# LED_Controller.net
KiCad netlist of a schematic drawn in EAGLE
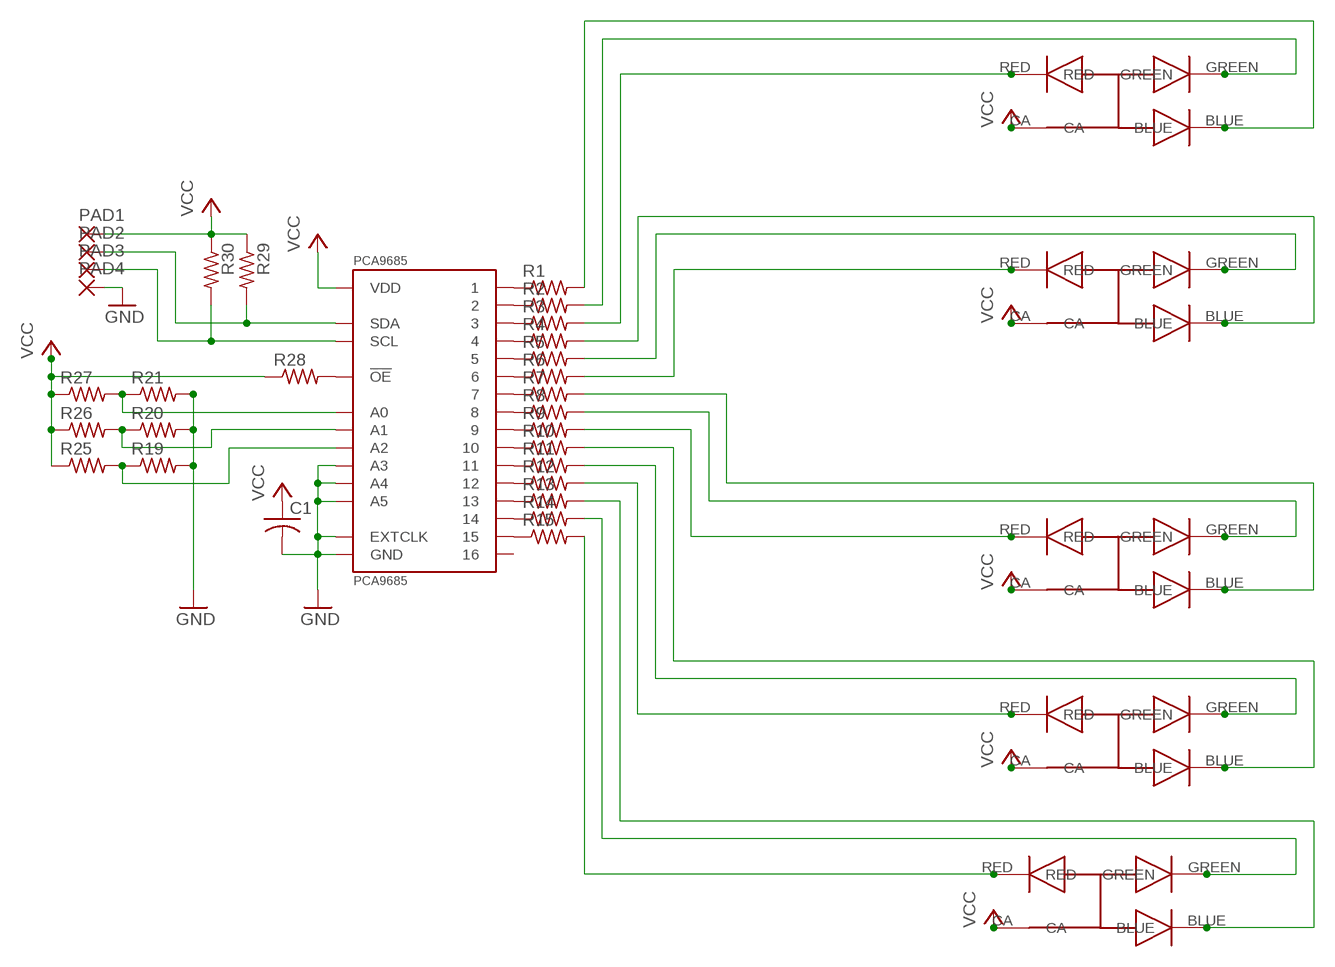
[diagram p0: schematic, sheet 1]

(export (version "E")
  (design (tool "Eeschema 10.0.6"))
  (components
    (comp (ref "C1")
      (value "C-USC0402")
      (footprint "eagle-import:C0402")
      (libsource (lib "eagle-import") (part "C-USC0402"))
    )
    (comp (ref "PAD1")
      (value "SMD2")
      (footprint "eagle-import:SMD1,27-2,54")
      (libsource (lib "eagle-import") (part "SMD2"))
    )
    (comp (ref "PAD2")
      (value "SMD2")
      (footprint "eagle-import:SMD1,27-2,54")
      (libsource (lib "eagle-import") (part "SMD2"))
    )
    (comp (ref "PAD3")
      (value "SMD2")
      (footprint "eagle-import:SMD1,27-2,54")
      (libsource (lib "eagle-import") (part "SMD2"))
    )
    (comp (ref "PAD4")
      (value "SMD2")
      (footprint "eagle-import:SMD1,27-2,54")
      (libsource (lib "eagle-import") (part "SMD2"))
    )
    (comp (ref "PCA9685")
      (value "PCA9685")
      (footprint "eagle-import:HVQFN28")
      (libsource (lib "eagle-import") (part "PCA9685"))
    )
    (comp (ref "R1")
      (value "R-US_R0402")
      (footprint "eagle-import:R0402")
      (libsource (lib "eagle-import") (part "R-US_R0402"))
    )
    (comp (ref "R2")
      (value "R-US_R0402")
      (footprint "eagle-import:R0402")
      (libsource (lib "eagle-import") (part "R-US_R0402"))
    )
    (comp (ref "R3")
      (value "R-US_R0402")
      (footprint "eagle-import:R0402")
      (libsource (lib "eagle-import") (part "R-US_R0402"))
    )
    (comp (ref "R4")
      (value "R-US_R0402")
      (footprint "eagle-import:R0402")
      (libsource (lib "eagle-import") (part "R-US_R0402"))
    )
    (comp (ref "R5")
      (value "R-US_R0402")
      (footprint "eagle-import:R0402")
      (libsource (lib "eagle-import") (part "R-US_R0402"))
    )
    (comp (ref "R6")
      (value "R-US_R0402")
      (footprint "eagle-import:R0402")
      (libsource (lib "eagle-import") (part "R-US_R0402"))
    )
    (comp (ref "R7")
      (value "R-US_R0402")
      (footprint "eagle-import:R0402")
      (libsource (lib "eagle-import") (part "R-US_R0402"))
    )
    (comp (ref "R8")
      (value "R-US_R0402")
      (footprint "eagle-import:R0402")
      (libsource (lib "eagle-import") (part "R-US_R0402"))
    )
    (comp (ref "R9")
      (value "R-US_R0402")
      (footprint "eagle-import:R0402")
      (libsource (lib "eagle-import") (part "R-US_R0402"))
    )
    (comp (ref "R10")
      (value "R-US_R0402")
      (footprint "eagle-import:R0402")
      (libsource (lib "eagle-import") (part "R-US_R0402"))
    )
    (comp (ref "R11")
      (value "R-US_R0402")
      (footprint "eagle-import:R0402")
      (libsource (lib "eagle-import") (part "R-US_R0402"))
    )
    (comp (ref "R12")
      (value "R-US_R0402")
      (footprint "eagle-import:R0402")
      (libsource (lib "eagle-import") (part "R-US_R0402"))
    )
    (comp (ref "R13")
      (value "R-US_R0402")
      (footprint "eagle-import:R0402")
      (libsource (lib "eagle-import") (part "R-US_R0402"))
    )
    (comp (ref "R14")
      (value "R-US_R0402")
      (footprint "eagle-import:R0402")
      (libsource (lib "eagle-import") (part "R-US_R0402"))
    )
    (comp (ref "R15")
      (value "R-US_R0402")
      (footprint "eagle-import:R0402")
      (libsource (lib "eagle-import") (part "R-US_R0402"))
    )
    (comp (ref "R19")
      (value "R-US_R0402")
      (footprint "eagle-import:R0402")
      (libsource (lib "eagle-import") (part "R-US_R0402"))
    )
    (comp (ref "R20")
      (value "R-US_R0402")
      (footprint "eagle-import:R0402")
      (libsource (lib "eagle-import") (part "R-US_R0402"))
    )
    (comp (ref "R21")
      (value "R-US_R0402")
      (footprint "eagle-import:R0402")
      (libsource (lib "eagle-import") (part "R-US_R0402"))
    )
    (comp (ref "R25")
      (value "R-US_R0402")
      (footprint "eagle-import:R0402")
      (libsource (lib "eagle-import") (part "R-US_R0402"))
    )
    (comp (ref "R26")
      (value "R-US_R0402")
      (footprint "eagle-import:R0402")
      (libsource (lib "eagle-import") (part "R-US_R0402"))
    )
    (comp (ref "R27")
      (value "R-US_R0402")
      (footprint "eagle-import:R0402")
      (libsource (lib "eagle-import") (part "R-US_R0402"))
    )
    (comp (ref "R28")
      (value "R-US_R0402")
      (footprint "eagle-import:R0402")
      (libsource (lib "eagle-import") (part "R-US_R0402"))
    )
    (comp (ref "R29")
      (value "R-US_R0402")
      (footprint "eagle-import:R0402")
      (libsource (lib "eagle-import") (part "R-US_R0402"))
    )
    (comp (ref "R30")
      (value "R-US_R0402")
      (footprint "eagle-import:R0402")
      (libsource (lib "eagle-import") (part "R-US_R0402"))
    )
    (comp (ref "U$2")
      (value "CLV1A-FKB")
      (footprint "eagle-import:CLV1A-FKB")
      (libsource (lib "eagle-import") (part "CLV1A-FKB"))
    )
    (comp (ref "U$3")
      (value "CLV1A-FKB")
      (footprint "eagle-import:CLV1A-FKB")
      (libsource (lib "eagle-import") (part "CLV1A-FKB"))
    )
    (comp (ref "U$4")
      (value "CLV1A-FKB")
      (footprint "eagle-import:CLV1A-FKB")
      (libsource (lib "eagle-import") (part "CLV1A-FKB"))
    )
    (comp (ref "U$5")
      (value "CLV1A-FKB")
      (footprint "eagle-import:CLV1A-FKB")
      (libsource (lib "eagle-import") (part "CLV1A-FKB"))
    )
    (comp (ref "U$6")
      (value "CLV1A-FKB")
      (footprint "eagle-import:CLV1A-FKB")
      (libsource (lib "eagle-import") (part "CLV1A-FKB"))
    )
  )
  (nets
    (net (code "1") (name "GND") (class "Default")
      (node (ref "C1") (pin "2") (pinfunction "2_2") (pintype "passive"))
      (node (ref "PAD4") (pin "1") (pinfunction "P_1") (pintype "passive"))
      (node (ref "PCA9685") (pin "14") (pinfunction "GND_14") (pintype "bidirectional"))
      (node (ref "PCA9685") (pin "24") (pinfunction "A5_24") (pintype "bidirectional"))
      (node (ref "PCA9685") (pin "25") (pinfunction "EXTCLK_25") (pintype "bidirectional"))
      (node (ref "PCA9685") (pin "4") (pinfunction "A3_4") (pintype "bidirectional"))
      (node (ref "PCA9685") (pin "5") (pinfunction "A4_5") (pintype "bidirectional"))
      (node (ref "PCA9685") (pin "PAD") (pinfunction "GND_PAD") (pintype "bidirectional"))
      (node (ref "R19") (pin "2") (pinfunction "2_2") (pintype "passive"))
      (node (ref "R20") (pin "2") (pinfunction "2_2") (pintype "passive"))
      (node (ref "R21") (pin "2") (pinfunction "2_2") (pintype "passive"))
    )
    (net (code "2") (name "Net-(PAD2-P)") (class "Default")
      (node (ref "PAD2") (pin "1") (pinfunction "P_1") (pintype "passive"))
      (node (ref "PCA9685") (pin "27") (pinfunction "SDA_27") (pintype "bidirectional"))
      (node (ref "R29") (pin "2") (pinfunction "2_2") (pintype "passive"))
    )
    (net (code "3") (name "Net-(PAD3-P)") (class "Default")
      (node (ref "PAD3") (pin "1") (pinfunction "P_1") (pintype "passive"))
      (node (ref "PCA9685") (pin "26") (pinfunction "SCL_26") (pintype "bidirectional"))
      (node (ref "R30") (pin "2") (pinfunction "2_2") (pintype "passive"))
    )
    (net (code "4") (name "Net-(PCA9685-1)") (class "Default")
      (node (ref "PCA9685") (pin "6") (pinfunction "1_6") (pintype "bidirectional"))
      (node (ref "R1") (pin "1") (pinfunction "1_1") (pintype "passive"))
    )
    (net (code "5") (name "Net-(PCA9685-2)") (class "Default")
      (node (ref "PCA9685") (pin "7") (pinfunction "2_7") (pintype "bidirectional"))
      (node (ref "R2") (pin "1") (pinfunction "1_1") (pintype "passive"))
    )
    (net (code "6") (name "Net-(PCA9685-3)") (class "Default")
      (node (ref "PCA9685") (pin "8") (pinfunction "3_8") (pintype "bidirectional"))
      (node (ref "R3") (pin "1") (pinfunction "1_1") (pintype "passive"))
    )
    (net (code "7") (name "Net-(PCA9685-4)") (class "Default")
      (node (ref "PCA9685") (pin "9") (pinfunction "4_9") (pintype "bidirectional"))
      (node (ref "R4") (pin "1") (pinfunction "1_1") (pintype "passive"))
    )
    (net (code "8") (name "Net-(PCA9685-5)") (class "Default")
      (node (ref "PCA9685") (pin "10") (pinfunction "5_10") (pintype "bidirectional"))
      (node (ref "R5") (pin "1") (pinfunction "1_1") (pintype "passive"))
    )
    (net (code "9") (name "Net-(PCA9685-6)") (class "Default")
      (node (ref "PCA9685") (pin "11") (pinfunction "6_11") (pintype "bidirectional"))
      (node (ref "R6") (pin "1") (pinfunction "1_1") (pintype "passive"))
    )
    (net (code "10") (name "Net-(PCA9685-7)") (class "Default")
      (node (ref "PCA9685") (pin "12") (pinfunction "7_12") (pintype "bidirectional"))
      (node (ref "R7") (pin "1") (pinfunction "1_1") (pintype "passive"))
    )
    (net (code "11") (name "Net-(PCA9685-8)") (class "Default")
      (node (ref "PCA9685") (pin "13") (pinfunction "8_13") (pintype "bidirectional"))
      (node (ref "R8") (pin "1") (pinfunction "1_1") (pintype "passive"))
    )
    (net (code "12") (name "Net-(PCA9685-9)") (class "Default")
      (node (ref "PCA9685") (pin "15") (pinfunction "9_15") (pintype "bidirectional"))
      (node (ref "R9") (pin "1") (pinfunction "1_1") (pintype "passive"))
    )
    (net (code "13") (name "Net-(PCA9685-10)") (class "Default")
      (node (ref "PCA9685") (pin "16") (pinfunction "10_16") (pintype "bidirectional"))
      (node (ref "R10") (pin "1") (pinfunction "1_1") (pintype "passive"))
    )
    (net (code "14") (name "Net-(PCA9685-11)") (class "Default")
      (node (ref "PCA9685") (pin "17") (pinfunction "11_17") (pintype "bidirectional"))
      (node (ref "R11") (pin "1") (pinfunction "1_1") (pintype "passive"))
    )
    (net (code "15") (name "Net-(PCA9685-12)") (class "Default")
      (node (ref "PCA9685") (pin "18") (pinfunction "12_18") (pintype "bidirectional"))
      (node (ref "R12") (pin "1") (pinfunction "1_1") (pintype "passive"))
    )
    (net (code "16") (name "Net-(PCA9685-13)") (class "Default")
      (node (ref "PCA9685") (pin "19") (pinfunction "13_19") (pintype "bidirectional"))
      (node (ref "R13") (pin "1") (pinfunction "1_1") (pintype "passive"))
    )
    (net (code "17") (name "Net-(PCA9685-14)") (class "Default")
      (node (ref "PCA9685") (pin "20") (pinfunction "14_20") (pintype "bidirectional"))
      (node (ref "R14") (pin "1") (pinfunction "1_1") (pintype "passive"))
    )
    (net (code "18") (name "Net-(PCA9685-15)") (class "Default")
      (node (ref "PCA9685") (pin "21") (pinfunction "15_21") (pintype "bidirectional"))
      (node (ref "R15") (pin "1") (pinfunction "1_1") (pintype "passive"))
    )
    (net (code "19") (name "Net-(PCA9685-A0)") (class "Default")
      (node (ref "PCA9685") (pin "1") (pinfunction "A0_1") (pintype "bidirectional"))
      (node (ref "R21") (pin "1") (pinfunction "1_1") (pintype "passive"))
      (node (ref "R27") (pin "2") (pinfunction "2_2") (pintype "passive"))
    )
    (net (code "20") (name "Net-(PCA9685-A1)") (class "Default")
      (node (ref "PCA9685") (pin "2") (pinfunction "A1_2") (pintype "bidirectional"))
      (node (ref "R20") (pin "1") (pinfunction "1_1") (pintype "passive"))
      (node (ref "R26") (pin "2") (pinfunction "2_2") (pintype "passive"))
    )
    (net (code "21") (name "Net-(PCA9685-A2)") (class "Default")
      (node (ref "PCA9685") (pin "3") (pinfunction "A2_3") (pintype "bidirectional"))
      (node (ref "R19") (pin "1") (pinfunction "1_1") (pintype "passive"))
      (node (ref "R25") (pin "2") (pinfunction "2_2") (pintype "passive"))
    )
    (net (code "22") (name "Net-(PCA9685-~{OE})") (class "Default")
      (node (ref "PCA9685") (pin "23") (pinfunction "~{OE}_23") (pintype "bidirectional"))
      (node (ref "R28") (pin "2") (pinfunction "2_2") (pintype "passive"))
    )
    (net (code "23") (name "Net-(R1-Pad2)") (class "Default")
      (node (ref "R1") (pin "2") (pinfunction "2_2") (pintype "passive"))
      (node (ref "U$6") (pin "BLUE") (pinfunction "BLUE_BLUE") (pintype "bidirectional"))
    )
    (net (code "24") (name "Net-(R2-Pad2)") (class "Default")
      (node (ref "R2") (pin "2") (pinfunction "2_2") (pintype "passive"))
      (node (ref "U$6") (pin "GREEN") (pinfunction "GREEN_GREEN") (pintype "bidirectional"))
    )
    (net (code "25") (name "Net-(R3-Pad2)") (class "Default")
      (node (ref "R3") (pin "2") (pinfunction "2_2") (pintype "passive"))
      (node (ref "U$6") (pin "RED") (pinfunction "RED_RED") (pintype "bidirectional"))
    )
    (net (code "26") (name "Net-(R4-Pad2)") (class "Default")
      (node (ref "R4") (pin "2") (pinfunction "2_2") (pintype "passive"))
      (node (ref "U$5") (pin "BLUE") (pinfunction "BLUE_BLUE") (pintype "bidirectional"))
    )
    (net (code "27") (name "Net-(R5-Pad2)") (class "Default")
      (node (ref "R5") (pin "2") (pinfunction "2_2") (pintype "passive"))
      (node (ref "U$5") (pin "GREEN") (pinfunction "GREEN_GREEN") (pintype "bidirectional"))
    )
    (net (code "28") (name "Net-(R6-Pad2)") (class "Default")
      (node (ref "R6") (pin "2") (pinfunction "2_2") (pintype "passive"))
      (node (ref "U$5") (pin "RED") (pinfunction "RED_RED") (pintype "bidirectional"))
    )
    (net (code "29") (name "Net-(R7-Pad2)") (class "Default")
      (node (ref "R7") (pin "2") (pinfunction "2_2") (pintype "passive"))
      (node (ref "U$4") (pin "BLUE") (pinfunction "BLUE_BLUE") (pintype "bidirectional"))
    )
    (net (code "30") (name "Net-(R8-Pad2)") (class "Default")
      (node (ref "R8") (pin "2") (pinfunction "2_2") (pintype "passive"))
      (node (ref "U$4") (pin "GREEN") (pinfunction "GREEN_GREEN") (pintype "bidirectional"))
    )
    (net (code "31") (name "Net-(R9-Pad2)") (class "Default")
      (node (ref "R9") (pin "2") (pinfunction "2_2") (pintype "passive"))
      (node (ref "U$4") (pin "RED") (pinfunction "RED_RED") (pintype "bidirectional"))
    )
    (net (code "32") (name "Net-(R10-Pad2)") (class "Default")
      (node (ref "R10") (pin "2") (pinfunction "2_2") (pintype "passive"))
      (node (ref "U$3") (pin "BLUE") (pinfunction "BLUE_BLUE") (pintype "bidirectional"))
    )
    (net (code "33") (name "Net-(R11-Pad2)") (class "Default")
      (node (ref "R11") (pin "2") (pinfunction "2_2") (pintype "passive"))
      (node (ref "U$3") (pin "GREEN") (pinfunction "GREEN_GREEN") (pintype "bidirectional"))
    )
    (net (code "34") (name "Net-(R12-Pad2)") (class "Default")
      (node (ref "R12") (pin "2") (pinfunction "2_2") (pintype "passive"))
      (node (ref "U$3") (pin "RED") (pinfunction "RED_RED") (pintype "bidirectional"))
    )
    (net (code "35") (name "Net-(R13-Pad2)") (class "Default")
      (node (ref "R13") (pin "2") (pinfunction "2_2") (pintype "passive"))
      (node (ref "U$2") (pin "BLUE") (pinfunction "BLUE_BLUE") (pintype "bidirectional"))
    )
    (net (code "36") (name "Net-(R14-Pad2)") (class "Default")
      (node (ref "R14") (pin "2") (pinfunction "2_2") (pintype "passive"))
      (node (ref "U$2") (pin "GREEN") (pinfunction "GREEN_GREEN") (pintype "bidirectional"))
    )
    (net (code "37") (name "Net-(R15-Pad2)") (class "Default")
      (node (ref "R15") (pin "2") (pinfunction "2_2") (pintype "passive"))
      (node (ref "U$2") (pin "RED") (pinfunction "RED_RED") (pintype "bidirectional"))
    )
    (net (code "38") (name "VCC") (class "Default")
      (node (ref "C1") (pin "1") (pinfunction "1_1") (pintype "passive"))
      (node (ref "PAD1") (pin "1") (pinfunction "P_1") (pintype "passive"))
      (node (ref "PCA9685") (pin "28") (pinfunction "VDD_28") (pintype "bidirectional"))
      (node (ref "R25") (pin "1") (pinfunction "1_1") (pintype "passive"))
      (node (ref "R26") (pin "1") (pinfunction "1_1") (pintype "passive"))
      (node (ref "R27") (pin "1") (pinfunction "1_1") (pintype "passive"))
      (node (ref "R28") (pin "1") (pinfunction "1_1") (pintype "passive"))
      (node (ref "R29") (pin "1") (pinfunction "1_1") (pintype "passive"))
      (node (ref "R30") (pin "1") (pinfunction "1_1") (pintype "passive"))
      (node (ref "U$2") (pin "CA") (pinfunction "CA_CA") (pintype "bidirectional"))
      (node (ref "U$3") (pin "CA") (pinfunction "CA_CA") (pintype "bidirectional"))
      (node (ref "U$4") (pin "CA") (pinfunction "CA_CA") (pintype "bidirectional"))
      (node (ref "U$5") (pin "CA") (pinfunction "CA_CA") (pintype "bidirectional"))
      (node (ref "U$6") (pin "CA") (pinfunction "CA_CA") (pintype "bidirectional"))
    )
    (net (code "39") (name "unconnected-(PCA9685-16-Pad22)") (class "Default")
      (node (ref "PCA9685") (pin "22") (pinfunction "16_22") (pintype "bidirectional"))
    )
  )
)
